# M660B.net
KiCad netlist of a schematic drawn in EAGLE
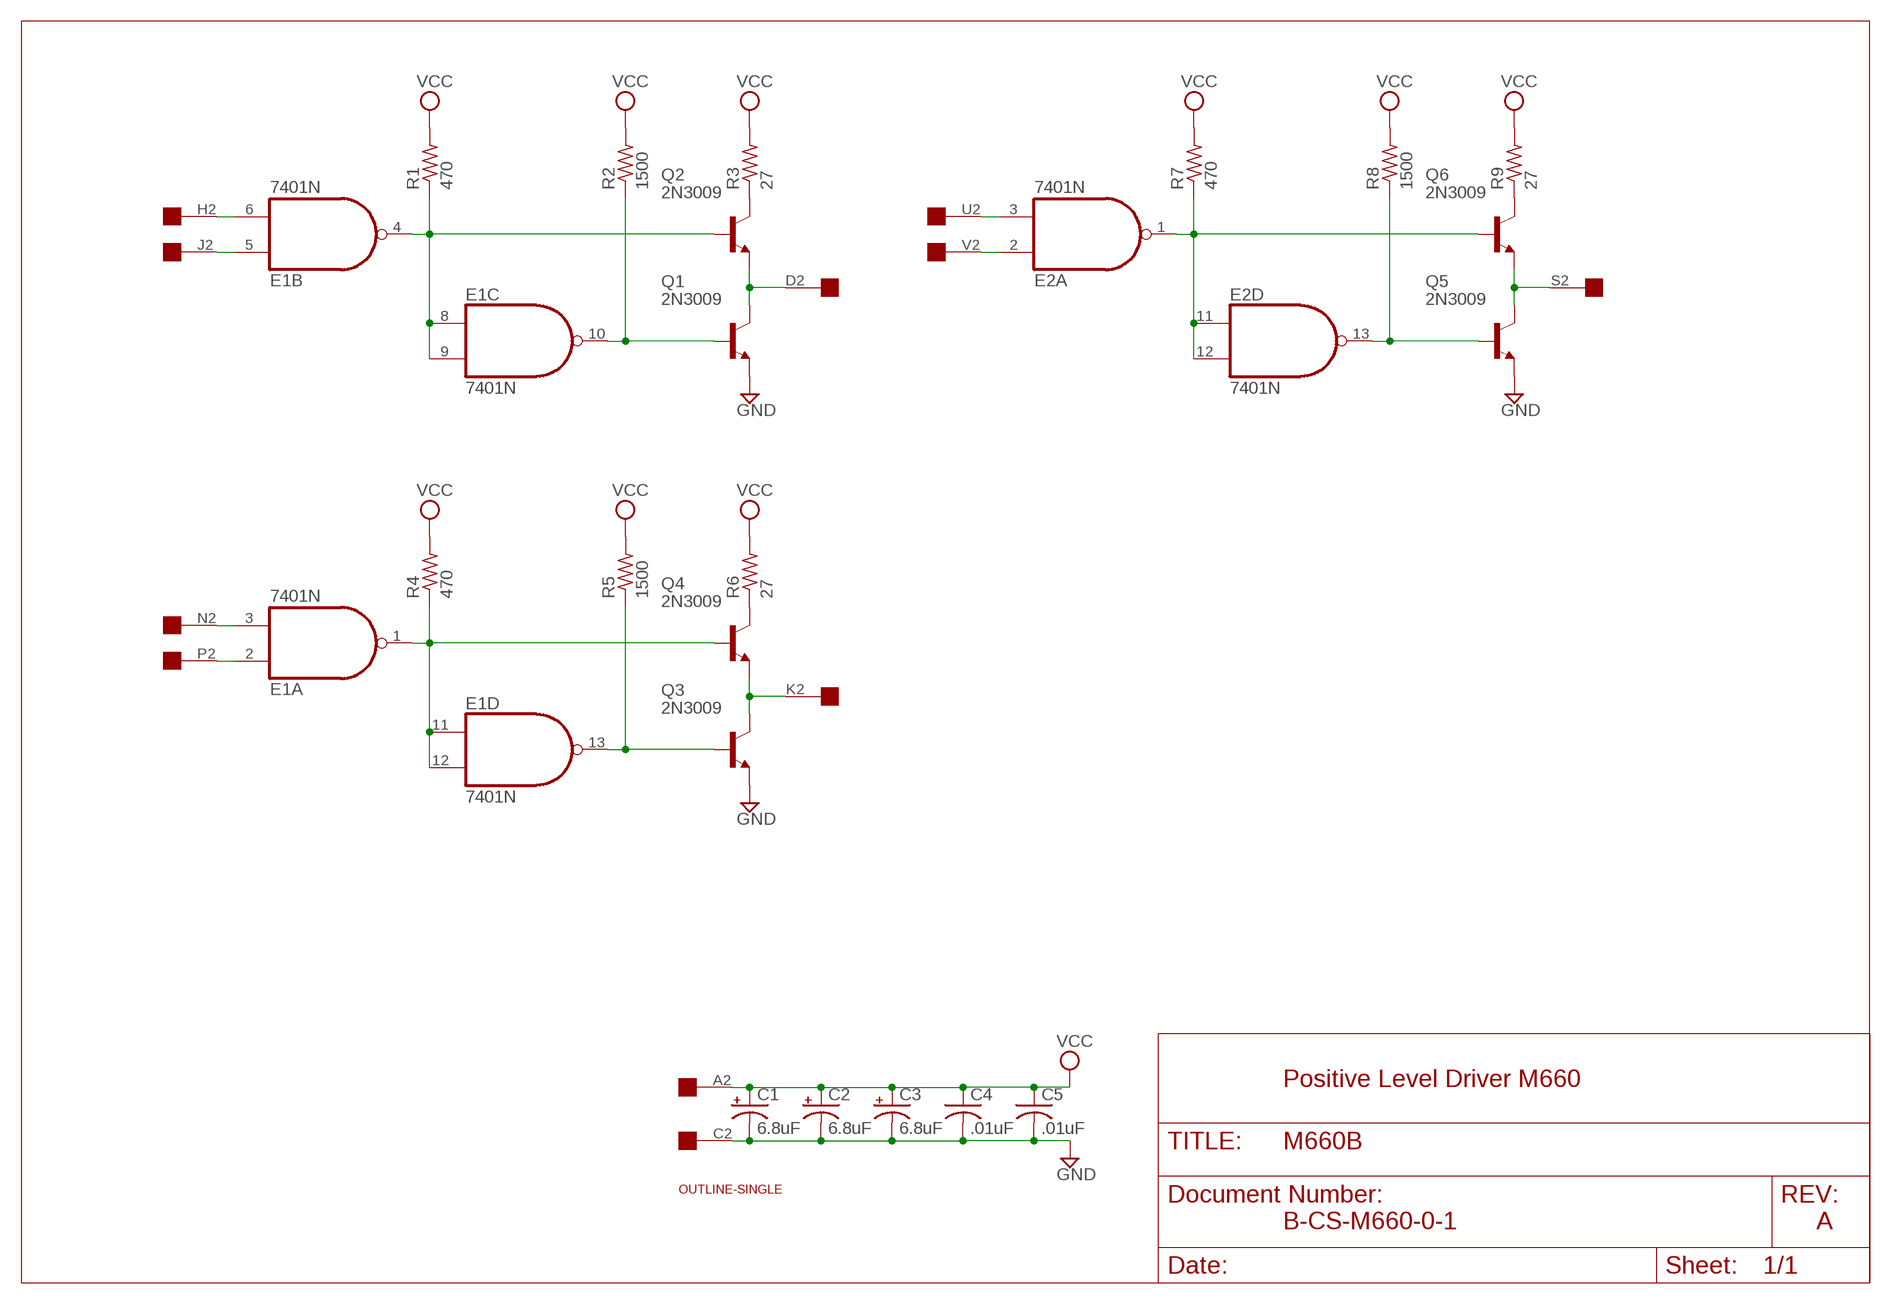
[diagram p0: schematic, sheet 1]

(export (version "E")
  (design (tool "Eeschema 10.0.6"))
  (components
    (comp (ref "C1")
      (value "6.8uF")
      (footprint "eagle-import:E15-5")
      (libsource (lib "eagle-import") (part "CPOL-USE15-5AXIAL"))
    )
    (comp (ref "C2")
      (value "6.8uF")
      (footprint "eagle-import:E15-5")
      (libsource (lib "eagle-import") (part "CPOL-USE15-5AXIAL"))
    )
    (comp (ref "C3")
      (value "6.8uF")
      (footprint "eagle-import:E15-5")
      (libsource (lib "eagle-import") (part "CPOL-USE15-5AXIAL"))
    )
    (comp (ref "C4")
      (value ".01uF")
      (footprint "eagle-import:C050-025X075")
      (libsource (lib "eagle-import") (part "C-US050-025X075"))
    )
    (comp (ref "C5")
      (value ".01uF")
      (footprint "eagle-import:C050-025X075")
      (libsource (lib "eagle-import") (part "C-US050-025X075"))
    )
    (comp (ref "E1")
      (value "7401N")
      (footprint "eagle-import:DIL14")
      (libsource (lib "eagle-import") (part "7401NLS"))
    )
    (comp (ref "E2")
      (value "7401N")
      (footprint "eagle-import:DIL14")
      (libsource (lib "eagle-import") (part "7401NLS"))
    )
    (comp (ref "Q1")
      (value "2N3009")
      (footprint "eagle-import:TO5")
      (libsource (lib "eagle-import") (part "2N2219"))
    )
    (comp (ref "Q2")
      (value "2N3009")
      (footprint "eagle-import:TO5")
      (libsource (lib "eagle-import") (part "2N2219"))
    )
    (comp (ref "Q3")
      (value "2N3009")
      (footprint "eagle-import:TO5")
      (libsource (lib "eagle-import") (part "2N2219"))
    )
    (comp (ref "Q4")
      (value "2N3009")
      (footprint "eagle-import:TO5")
      (libsource (lib "eagle-import") (part "2N2219"))
    )
    (comp (ref "Q5")
      (value "2N3009")
      (footprint "eagle-import:TO5")
      (libsource (lib "eagle-import") (part "2N2219"))
    )
    (comp (ref "Q6")
      (value "2N3009")
      (footprint "eagle-import:TO5")
      (libsource (lib "eagle-import") (part "2N2219"))
    )
    (comp (ref "R1")
      (value "470")
      (footprint "eagle-import:0207_10")
      (libsource (lib "eagle-import") (part "R-US_0207/10"))
    )
    (comp (ref "R2")
      (value "1500")
      (footprint "eagle-import:0207_10")
      (libsource (lib "eagle-import") (part "R-US_0207/10"))
    )
    (comp (ref "R3")
      (value "27")
      (footprint "eagle-import:0411_15")
      (libsource (lib "eagle-import") (part "R-US_0411/15"))
    )
    (comp (ref "R4")
      (value "470")
      (footprint "eagle-import:0207_10")
      (libsource (lib "eagle-import") (part "R-US_0207/10"))
    )
    (comp (ref "R5")
      (value "1500")
      (footprint "eagle-import:0207_10")
      (libsource (lib "eagle-import") (part "R-US_0207/10"))
    )
    (comp (ref "R6")
      (value "27")
      (footprint "eagle-import:0411_15")
      (libsource (lib "eagle-import") (part "R-US_0411/15"))
    )
    (comp (ref "R7")
      (value "470")
      (footprint "eagle-import:0207_10")
      (libsource (lib "eagle-import") (part "R-US_0207/10"))
    )
    (comp (ref "R8")
      (value "1500")
      (footprint "eagle-import:0207_10")
      (libsource (lib "eagle-import") (part "R-US_0207/10"))
    )
    (comp (ref "R9")
      (value "27")
      (footprint "eagle-import:0411_15")
      (libsource (lib "eagle-import") (part "R-US_0411/15"))
    )
    (comp (ref "U$1")
      (value "OUTLINE-SINGLE")
      (footprint "eagle-import:SINGLE")
      (libsource (lib "eagle-import") (part "OUTLINE-SINGLE"))
    )
    (comp (ref "U$3")
      (value "EDGE-1")
      (footprint "eagle-import:EDGE-CON1")
      (libsource (lib "eagle-import") (part "EDGE-1"))
    )
  )
  (nets
    (net (code "1") (name "GND") (class "Default")
      (node (ref "C1") (pin "-") (pinfunction "-_-") (pintype "passive"))
      (node (ref "C2") (pin "-") (pinfunction "-_-") (pintype "passive"))
      (node (ref "C3") (pin "-") (pinfunction "-_-") (pintype "passive"))
      (node (ref "C4") (pin "2") (pinfunction "2_2") (pintype "passive"))
      (node (ref "C5") (pin "2") (pinfunction "2_2") (pintype "passive"))
      (node (ref "Q1") (pin "1") (pinfunction "E_1") (pintype "passive"))
      (node (ref "Q3") (pin "1") (pinfunction "E_1") (pintype "passive"))
      (node (ref "Q5") (pin "1") (pinfunction "E_1") (pintype "passive"))
      (node (ref "U$3") (pin "C2") (pinfunction "1_C2") (pintype "bidirectional"))
    )
    (net (code "2") (name "Net-(E1A-I0)") (class "Default")
      (node (ref "E1") (pin "2") (pinfunction "I0_2") (pintype "input"))
      (node (ref "U$3") (pin "P2") (pinfunction "1_P2") (pintype "bidirectional"))
    )
    (net (code "3") (name "Net-(E1A-I1)") (class "Default")
      (node (ref "E1") (pin "3") (pinfunction "I1_3") (pintype "input"))
      (node (ref "U$3") (pin "N2") (pinfunction "1_N2") (pintype "bidirectional"))
    )
    (net (code "4") (name "Net-(E1A-O)") (class "Default")
      (node (ref "E1") (pin "1") (pinfunction "O_1") (pintype "open_collector"))
      (node (ref "E1") (pin "11") (pinfunction "I0_11") (pintype "input"))
      (node (ref "E1") (pin "12") (pinfunction "I1_12") (pintype "input"))
      (node (ref "Q4") (pin "2") (pinfunction "B_2") (pintype "passive"))
      (node (ref "R4") (pin "1") (pinfunction "1_1") (pintype "passive"))
    )
    (net (code "5") (name "Net-(E1B-I0)") (class "Default")
      (node (ref "E1") (pin "5") (pinfunction "I0_5") (pintype "input"))
      (node (ref "U$3") (pin "J2") (pinfunction "1_J2") (pintype "bidirectional"))
    )
    (net (code "6") (name "Net-(E1B-I1)") (class "Default")
      (node (ref "E1") (pin "6") (pinfunction "I1_6") (pintype "input"))
      (node (ref "U$3") (pin "H2") (pinfunction "1_H2") (pintype "bidirectional"))
    )
    (net (code "7") (name "Net-(E1B-O)") (class "Default")
      (node (ref "E1") (pin "4") (pinfunction "O_4") (pintype "open_collector"))
      (node (ref "E1") (pin "8") (pinfunction "I0_8") (pintype "input"))
      (node (ref "E1") (pin "9") (pinfunction "I1_9") (pintype "input"))
      (node (ref "Q2") (pin "2") (pinfunction "B_2") (pintype "passive"))
      (node (ref "R1") (pin "1") (pinfunction "1_1") (pintype "passive"))
    )
    (net (code "8") (name "Net-(E1C-O)") (class "Default")
      (node (ref "E1") (pin "10") (pinfunction "O_10") (pintype "open_collector"))
      (node (ref "Q1") (pin "2") (pinfunction "B_2") (pintype "passive"))
      (node (ref "R2") (pin "1") (pinfunction "1_1") (pintype "passive"))
    )
    (net (code "9") (name "Net-(E1D-O)") (class "Default")
      (node (ref "E1") (pin "13") (pinfunction "O_13") (pintype "open_collector"))
      (node (ref "Q3") (pin "2") (pinfunction "B_2") (pintype "passive"))
      (node (ref "R5") (pin "1") (pinfunction "1_1") (pintype "passive"))
    )
    (net (code "10") (name "Net-(E2A-I0)") (class "Default")
      (node (ref "E2") (pin "2") (pinfunction "I0_2") (pintype "input"))
      (node (ref "U$3") (pin "V2") (pinfunction "1_V2") (pintype "bidirectional"))
    )
    (net (code "11") (name "Net-(E2A-I1)") (class "Default")
      (node (ref "E2") (pin "3") (pinfunction "I1_3") (pintype "input"))
      (node (ref "U$3") (pin "U2") (pinfunction "1_U2") (pintype "bidirectional"))
    )
    (net (code "12") (name "Net-(E2A-O)") (class "Default")
      (node (ref "E2") (pin "1") (pinfunction "O_1") (pintype "open_collector"))
      (node (ref "E2") (pin "11") (pinfunction "I0_11") (pintype "input"))
      (node (ref "E2") (pin "12") (pinfunction "I1_12") (pintype "input"))
      (node (ref "Q6") (pin "2") (pinfunction "B_2") (pintype "passive"))
      (node (ref "R7") (pin "1") (pinfunction "1_1") (pintype "passive"))
    )
    (net (code "13") (name "Net-(E2D-O)") (class "Default")
      (node (ref "E2") (pin "13") (pinfunction "O_13") (pintype "open_collector"))
      (node (ref "Q5") (pin "2") (pinfunction "B_2") (pintype "passive"))
      (node (ref "R8") (pin "1") (pinfunction "1_1") (pintype "passive"))
    )
    (net (code "14") (name "Net-(Q1-C)") (class "Default")
      (node (ref "Q1") (pin "3") (pinfunction "C_3") (pintype "passive"))
      (node (ref "Q2") (pin "1") (pinfunction "E_1") (pintype "passive"))
      (node (ref "U$3") (pin "D2") (pinfunction "1_D2") (pintype "bidirectional"))
    )
    (net (code "15") (name "Net-(Q2-C)") (class "Default")
      (node (ref "Q2") (pin "3") (pinfunction "C_3") (pintype "passive"))
      (node (ref "R3") (pin "1") (pinfunction "1_1") (pintype "passive"))
    )
    (net (code "16") (name "Net-(Q3-C)") (class "Default")
      (node (ref "Q3") (pin "3") (pinfunction "C_3") (pintype "passive"))
      (node (ref "Q4") (pin "1") (pinfunction "E_1") (pintype "passive"))
      (node (ref "U$3") (pin "K2") (pinfunction "1_K2") (pintype "bidirectional"))
    )
    (net (code "17") (name "Net-(Q4-C)") (class "Default")
      (node (ref "Q4") (pin "3") (pinfunction "C_3") (pintype "passive"))
      (node (ref "R6") (pin "1") (pinfunction "1_1") (pintype "passive"))
    )
    (net (code "18") (name "Net-(Q5-C)") (class "Default")
      (node (ref "Q5") (pin "3") (pinfunction "C_3") (pintype "passive"))
      (node (ref "Q6") (pin "1") (pinfunction "E_1") (pintype "passive"))
      (node (ref "U$3") (pin "S2") (pinfunction "1_S2") (pintype "bidirectional"))
    )
    (net (code "19") (name "Net-(Q6-C)") (class "Default")
      (node (ref "Q6") (pin "3") (pinfunction "C_3") (pintype "passive"))
      (node (ref "R9") (pin "1") (pinfunction "1_1") (pintype "passive"))
    )
    (net (code "20") (name "VCC") (class "Default")
      (node (ref "C1") (pin "+") (pinfunction "+_+") (pintype "passive"))
      (node (ref "C2") (pin "+") (pinfunction "+_+") (pintype "passive"))
      (node (ref "C3") (pin "+") (pinfunction "+_+") (pintype "passive"))
      (node (ref "C4") (pin "1") (pinfunction "1_1") (pintype "passive"))
      (node (ref "C5") (pin "1") (pinfunction "1_1") (pintype "passive"))
      (node (ref "R1") (pin "2") (pinfunction "2_2") (pintype "passive"))
      (node (ref "R2") (pin "2") (pinfunction "2_2") (pintype "passive"))
      (node (ref "R3") (pin "2") (pinfunction "2_2") (pintype "passive"))
      (node (ref "R4") (pin "2") (pinfunction "2_2") (pintype "passive"))
      (node (ref "R5") (pin "2") (pinfunction "2_2") (pintype "passive"))
      (node (ref "R6") (pin "2") (pinfunction "2_2") (pintype "passive"))
      (node (ref "R7") (pin "2") (pinfunction "2_2") (pintype "passive"))
      (node (ref "R8") (pin "2") (pinfunction "2_2") (pintype "passive"))
      (node (ref "R9") (pin "2") (pinfunction "2_2") (pintype "passive"))
      (node (ref "U$3") (pin "A2") (pinfunction "1_A2") (pintype "bidirectional"))
    )
  )
)
